# OS-2024-Badge-Schematic-REV1.net
KiCad netlist of a schematic drawn in Altium Designer
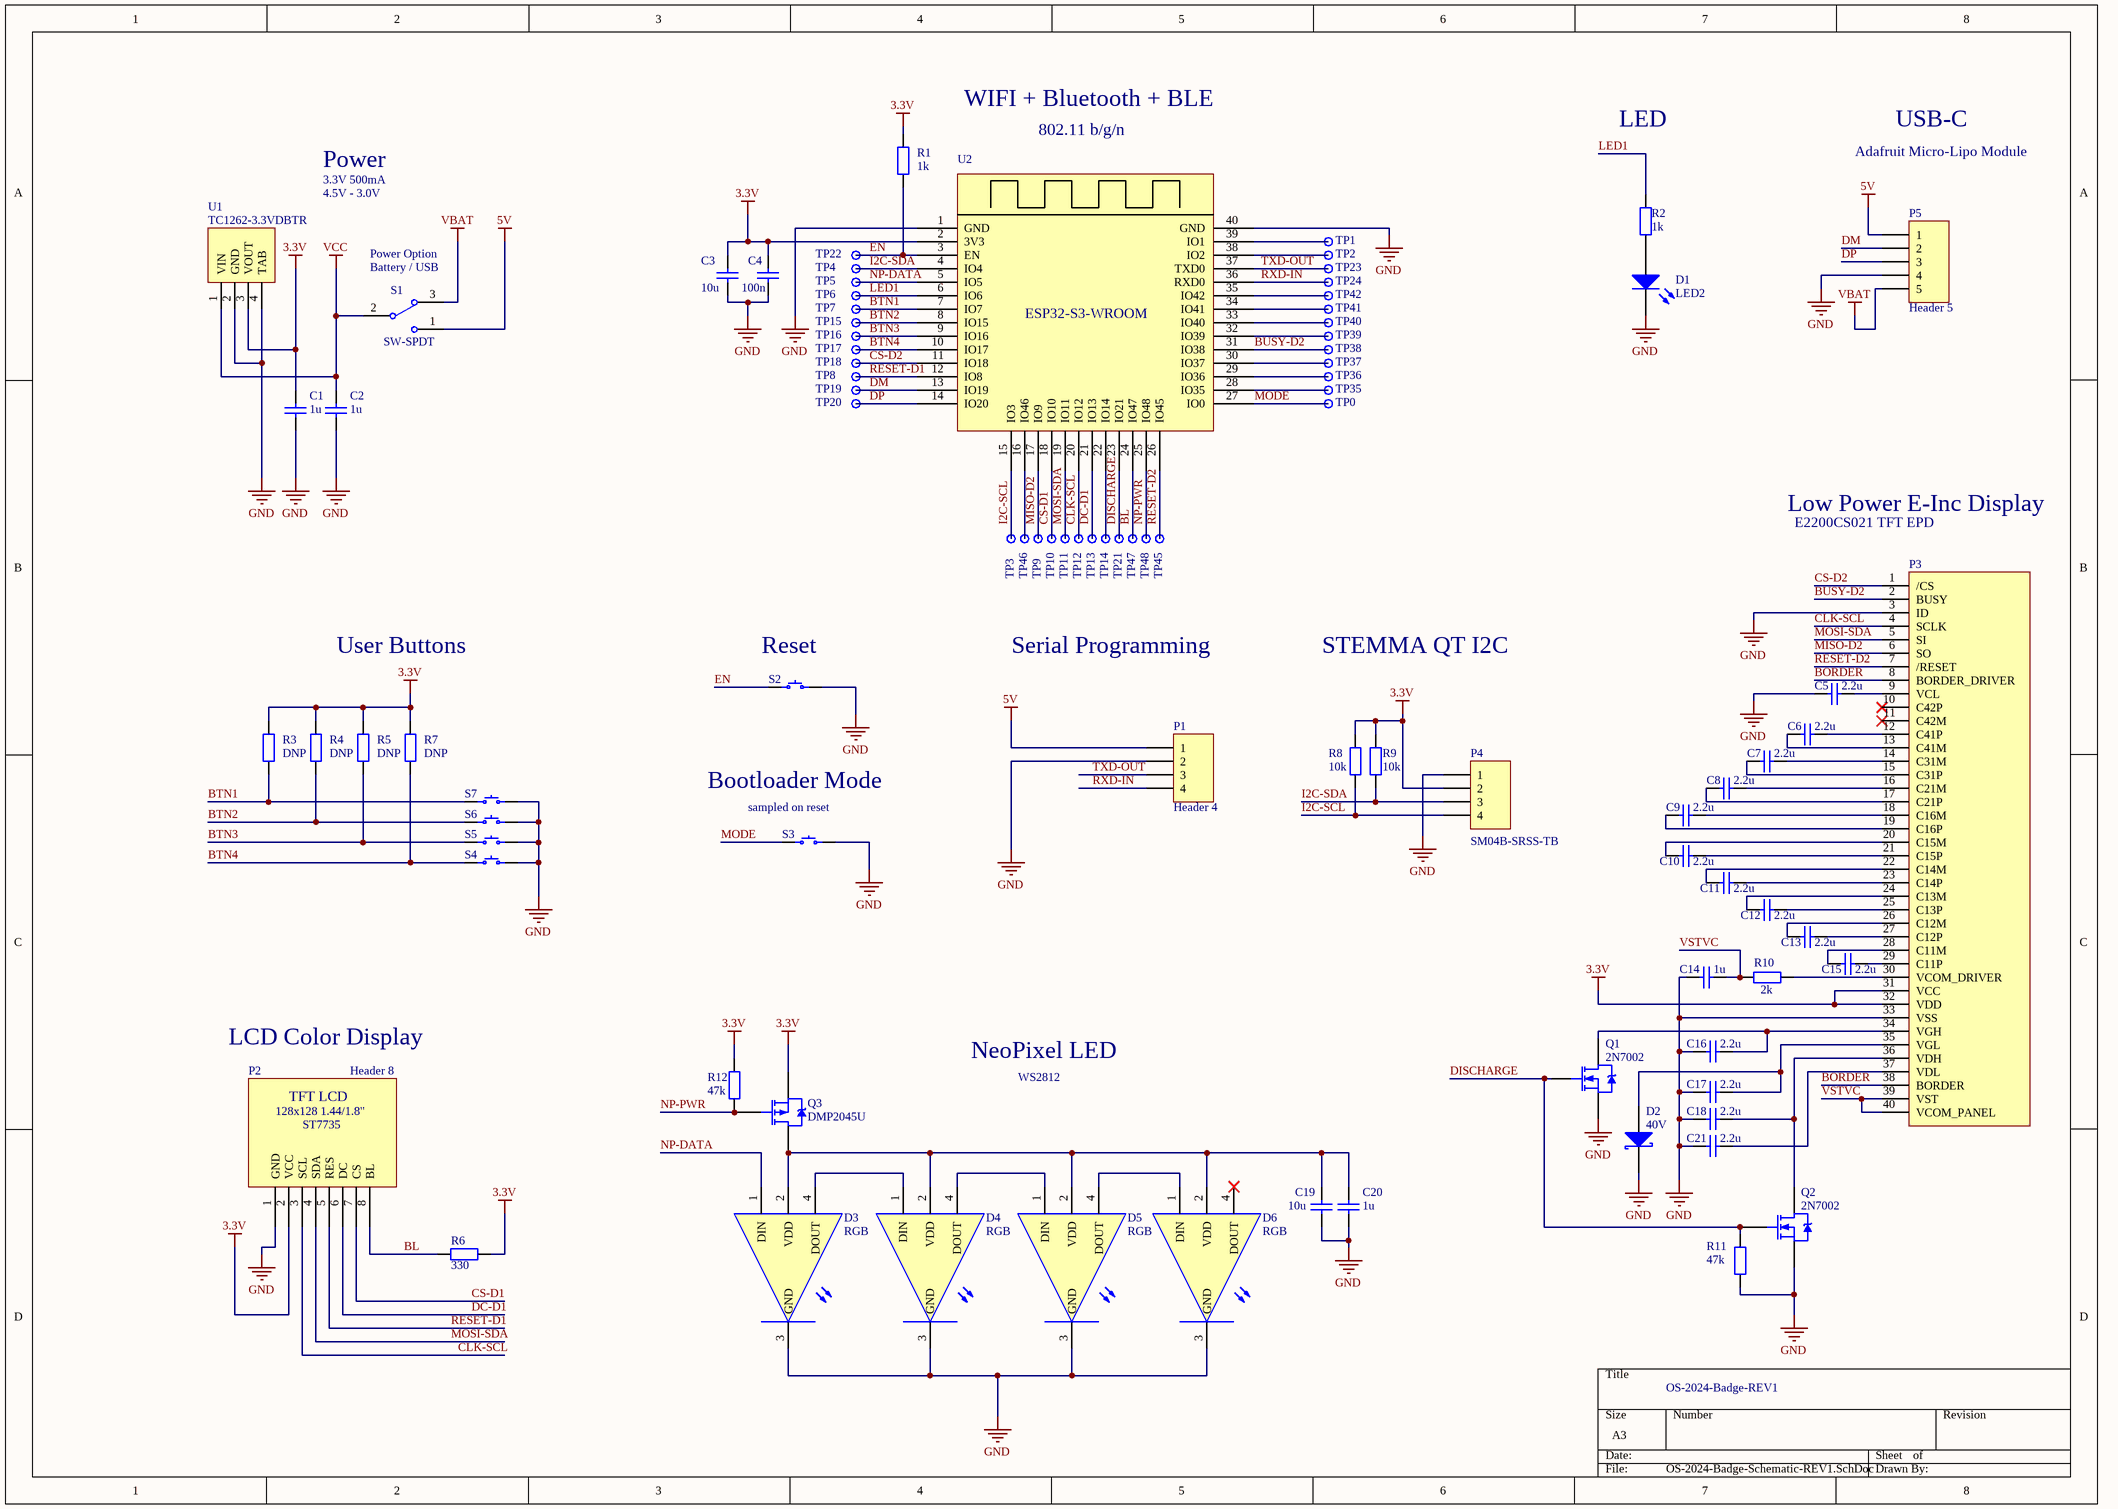
[diagram p0: OS-2024-Badge-Schematic-REV1.SchDoc]

(export (version "E")
  (design (tool "Eeschema 10.0.6"))
  (components
    (comp (ref "C1")
      (value "1u")
      (footprint "0603C")
      (description "CAP CER 1UF 50V Z5U 0603")
      (fields
        (field (name "MANUFACTURER") "Murata Electronics North America")
        (field (name "MANUFACTURER PART NUMBER") "GRT188R61H105ME13D")
      )
      (libsource (lib "Miscellaneous Devices") (part "Cap"))
    )
    (comp (ref "C2")
      (value "1u")
      (footprint "0603C")
      (description "CAP CER 1UF 50V Z5U 0603")
      (fields
        (field (name "MANUFACTURER") "Murata Electronics North America")
        (field (name "MANUFACTURER PART NUMBER") "GRT188R61H105ME13D")
      )
      (libsource (lib "Miscellaneous Devices") (part "Cap"))
    )
    (comp (ref "C3")
      (value "10u")
      (footprint "0603C")
      (description "CAP CER 10UF 10V X5R 0603")
      (fields
        (field (name "MANUFACTURER") "Murata Electronics North America")
        (field (name "MANUFACTURER PART NUMBER") "GRN188R61A106KE69J")
      )
      (libsource (lib "Miscellaneous Devices") (part "Cap"))
    )
    (comp (ref "C4")
      (value "100n")
      (footprint "0603C")
      (description "CAP CER .1UF 10V X7R 0603")
      (fields
        (field (name "MANUFACTURER") "Wurth Electronics Inc.")
        (field (name "MANUFACTURER PART NUMBER") "885012206020")
      )
      (libsource (lib "Miscellaneous Devices") (part "Cap"))
    )
    (comp (ref "C5")
      (value "2.2u")
      (footprint "0603C")
      (description "CAP CER 2.2UF 10V X5R 0603")
      (fields
        (field (name "MANUFACTURER") "Cal-Chip Electronics, Inc.")
        (field (name "MANUFACTURER PART NUMBER") "GMC10X5R225M10NT")
      )
      (libsource (lib "Miscellaneous Devices") (part "Cap"))
    )
    (comp (ref "C6")
      (value "2.2u")
      (footprint "0603C")
      (description "CAP CER 2.2UF 10V X5R 0603")
      (fields
        (field (name "MANUFACTURER") "Cal-Chip Electronics, Inc.")
        (field (name "MANUFACTURER PART NUMBER") "GMC10X5R225M10NT")
      )
      (libsource (lib "Miscellaneous Devices") (part "Cap"))
    )
    (comp (ref "C7")
      (value "2.2u")
      (footprint "0603C")
      (description "CAP CER 2.2UF 10V X5R 0603")
      (fields
        (field (name "MANUFACTURER") "Cal-Chip Electronics, Inc.")
        (field (name "MANUFACTURER PART NUMBER") "GMC10X5R225M10NT")
      )
      (libsource (lib "Miscellaneous Devices") (part "Cap"))
    )
    (comp (ref "C8")
      (value "2.2u")
      (footprint "0603C")
      (description "CAP CER 2.2UF 10V X5R 0603")
      (fields
        (field (name "MANUFACTURER") "Cal-Chip Electronics, Inc.")
        (field (name "MANUFACTURER PART NUMBER") "GMC10X5R225M10NT")
      )
      (libsource (lib "Miscellaneous Devices") (part "Cap"))
    )
    (comp (ref "C9")
      (value "2.2u")
      (footprint "0603C")
      (description "CAP CER 2.2UF 10V X5R 0603")
      (fields
        (field (name "MANUFACTURER") "Cal-Chip Electronics, Inc.")
        (field (name "MANUFACTURER PART NUMBER") "GMC10X5R225M10NT")
      )
      (libsource (lib "Miscellaneous Devices") (part "Cap"))
    )
    (comp (ref "C10")
      (value "2.2u")
      (footprint "0603C")
      (description "CAP CER 2.2UF 10V X5R 0603")
      (fields
        (field (name "MANUFACTURER") "Cal-Chip Electronics, Inc.")
        (field (name "MANUFACTURER PART NUMBER") "GMC10X5R225M10NT")
      )
      (libsource (lib "Miscellaneous Devices") (part "Cap"))
    )
    (comp (ref "C11")
      (value "2.2u")
      (footprint "0603C")
      (description "CAP CER 2.2UF 10V X5R 0603")
      (fields
        (field (name "MANUFACTURER") "Cal-Chip Electronics, Inc.")
        (field (name "MANUFACTURER PART NUMBER") "GMC10X5R225M10NT")
      )
      (libsource (lib "Miscellaneous Devices") (part "Cap"))
    )
    (comp (ref "C12")
      (value "2.2u")
      (footprint "0603C")
      (description "CAP CER 2.2UF 10V X5R 0603")
      (fields
        (field (name "MANUFACTURER") "Cal-Chip Electronics, Inc.")
        (field (name "MANUFACTURER PART NUMBER") "GMC10X5R225M10NT")
      )
      (libsource (lib "Miscellaneous Devices") (part "Cap"))
    )
    (comp (ref "C13")
      (value "2.2u")
      (footprint "0603C")
      (description "CAP CER 2.2UF 10V X5R 0603")
      (fields
        (field (name "MANUFACTURER") "Cal-Chip Electronics, Inc.")
        (field (name "MANUFACTURER PART NUMBER") "GMC10X5R225M10NT")
      )
      (libsource (lib "Miscellaneous Devices") (part "Cap"))
    )
    (comp (ref "C14")
      (value "1u")
      (footprint "0603C")
      (description "CAP CER 1UF 50V Z5U 0603")
      (fields
        (field (name "MANUFACTURER") "Murata Electronics North America")
        (field (name "MANUFACTURER PART NUMBER") "GRT188R61H105ME13D")
      )
      (libsource (lib "Miscellaneous Devices") (part "Cap"))
    )
    (comp (ref "C15")
      (value "2.2u")
      (footprint "0603C")
      (description "CAP CER 2.2UF 10V X5R 0603")
      (fields
        (field (name "MANUFACTURER") "Cal-Chip Electronics, Inc.")
        (field (name "MANUFACTURER PART NUMBER") "GMC10X5R225M10NT")
      )
      (libsource (lib "Miscellaneous Devices") (part "Cap"))
    )
    (comp (ref "C16")
      (value "2.2u")
      (footprint "0603C")
      (description "CAP CER 2.2UF 10V X5R 0603")
      (fields
        (field (name "MANUFACTURER") "Cal-Chip Electronics, Inc.")
        (field (name "MANUFACTURER PART NUMBER") "GMC10X5R225M10NT")
      )
      (libsource (lib "Miscellaneous Devices") (part "Cap"))
    )
    (comp (ref "C17")
      (value "2.2u")
      (footprint "0603C")
      (description "CAP CER 2.2UF 10V X5R 0603")
      (fields
        (field (name "MANUFACTURER") "Cal-Chip Electronics, Inc.")
        (field (name "MANUFACTURER PART NUMBER") "GMC10X5R225M10NT")
      )
      (libsource (lib "Miscellaneous Devices") (part "Cap"))
    )
    (comp (ref "C18")
      (value "2.2u")
      (footprint "0603C")
      (description "CAP CER 2.2UF 10V X5R 0603")
      (fields
        (field (name "MANUFACTURER") "Cal-Chip Electronics, Inc.")
        (field (name "MANUFACTURER PART NUMBER") "GMC10X5R225M10NT")
      )
      (libsource (lib "Miscellaneous Devices") (part "Cap"))
    )
    (comp (ref "C19")
      (value "10u")
      (footprint "0603C")
      (description "CAP CER 10UF 10V X5R 0603")
      (fields
        (field (name "MANUFACTURER") "Murata Electronics North America")
        (field (name "MANUFACTURER PART NUMBER") "GRN188R61A106KE69J")
      )
      (libsource (lib "Miscellaneous Devices") (part "Cap"))
    )
    (comp (ref "C20")
      (value "1u")
      (footprint "0603C")
      (description "CAP CER 1UF 50V Z5U 0603")
      (fields
        (field (name "MANUFACTURER") "Murata Electronics North America")
        (field (name "MANUFACTURER PART NUMBER") "GRT188R61H105ME13D")
      )
      (libsource (lib "Miscellaneous Devices") (part "Cap"))
    )
    (comp (ref "C21")
      (value "2.2u")
      (footprint "0603C")
      (description "CAP CER 2.2UF 10V X5R 0603")
      (fields
        (field (name "MANUFACTURER") "Cal-Chip Electronics, Inc.")
        (field (name "MANUFACTURER PART NUMBER") "GMC10X5R225M10NT")
      )
      (libsource (lib "Miscellaneous Devices") (part "Cap"))
    )
    (comp (ref "D1")
      (value "LED2")
      (footprint "0603LED")
      (description "LED ORANGE CLEAR CHIP SMD")
      (fields
        (field (name "DISTRIBUTOR PART NUMBER") "754-1120-1-ND")
        (field (name "MANUFACTURER") "Kingbright")
      )
      (libsource (lib "Miscellaneous Devices") (part "LED2"))
    )
    (comp (ref "D2")
      (value "40V")
      (footprint "SOD-123FL")
      (description "DIODE SCHOTTKY 40V 2A SOD123FL")
      (fields
        (field (name "DISTRIBUTOR PART NUMBER") "3757-SS2040FL_R1_00001CT-ND")
        (field (name "MANUFACTURER") "Panjit International Inc.")
      )
      (libsource (lib "Miscellaneous Devices") (part "Diode BAT17"))
    )
    (comp (ref "D3")
      (value "RGB")
      (footprint "COM-12986")
      (description "ADDRESS LED DISCR SERIAL RGB")
      (fields
        (field (name "DISTRIBUTOR PART NUMBER") "1568-1213-ND")
        (field (name "MANUFACTURER") "Spark Fun")
      )
      (libsource (lib "2024-Badge-Altium-Project-REV0_1") (part "LED2_1"))
    )
    (comp (ref "D4")
      (value "RGB")
      (footprint "COM-12986")
      (description "ADDRESS LED DISCR SERIAL RGB")
      (fields
        (field (name "DISTRIBUTOR PART NUMBER") "1568-1213-ND")
        (field (name "MANUFACTURER") "Spark Fun")
      )
      (libsource (lib "2024-Badge-Altium-Project-REV0_1") (part "LED2_1"))
    )
    (comp (ref "D5")
      (value "RGB")
      (footprint "COM-12986")
      (description "ADDRESS LED DISCR SERIAL RGB")
      (fields
        (field (name "DISTRIBUTOR PART NUMBER") "1568-1213-ND")
        (field (name "MANUFACTURER") "Spark Fun")
      )
      (libsource (lib "2024-Badge-Altium-Project-REV0_1") (part "LED2_1"))
    )
    (comp (ref "D6")
      (value "RGB")
      (footprint "COM-12986")
      (description "ADDRESS LED DISCR SERIAL RGB")
      (fields
        (field (name "DISTRIBUTOR PART NUMBER") "1568-1213-ND")
        (field (name "MANUFACTURER") "Spark Fun")
      )
      (libsource (lib "2024-Badge-Altium-Project-REV0_1") (part "LED2_1"))
    )
    (comp (ref "P1")
      (value "Header 4")
      (footprint "HDR1X4")
      (description "Header, 4-Pin")
      (fields
        (field (name "DISTRIBUTOR PART NUMBER") "732-5317-ND")
        (field (name "MANUFACTURER") "Wurth Elektronik")
      )
      (libsource (lib "Miscellaneous Connectors") (part "Header 4"))
    )
    (comp (ref "P2")
      (value "Header 8")
      (footprint "TFT144SPI")
      (description "1.44\" 128x128 65K SPI Full Color TFT LCD Display Module ST7735 OLED for Arduino")
      (fields (field (name "DISTRIBUTOR PART NUMBER") "ED90446-ND") (field (name "MANUFACTURER") "Mill-Max"))
      (libsource (lib "OS-2019-Badge-Schematic-REV0") (part "Display_128_128"))
    )
    (comp (ref "P3")
      (value "CONN FPC BOTTOM 40POS 0.5MM R/A")
      (footprint "AMPHENOL_62684-401100AHLF")
      (fields
        (field (name "DISTRIBUTOR PART NUMBER") "609-62684-401100AHLFTR-ND")
        (field (name "MANUFACTURER") "Amphenol ICC (FCI)")
        (field (name "MANUFACTURER PART NUMBER") "62684-401100AHLF")
      )
      (libsource (lib "2024-Badge-Altium-Project-REV1") (part "Header 40"))
    )
    (comp (ref "P4")
      (value "SM04B-SRSS-TB")
      (footprint "SM04B-TRSS-TB")
      (description "CONN HEADER SMD R/A 4POS 1MM")
      (fields
        (field (name "DISTRIBUTOR PART NUMBER") "455-SM04B-SRSS-TBCT-ND")
        (field (name "MANUFACTURER") "JST Sales America Inc.")
      )
      (libsource (lib "2024-Badge-Altium-Project-REV0_1") (part "Header 5"))
    )
    (comp (ref "P5")
      (value "Header 5")
      (footprint "Micro-Lipo-USBC")
      (description "Adafruit Micro-Lipo Charger for LiPoly Batt with USB Type C Jack")
      (fields (field (name "DISTRIBUTOR PART NUMBER") "ED90446-ND") (field (name "MANUFACTURER") "Mill-Max"))
      (libsource (lib "Miscellaneous Connectors") (part "Header 5"))
    )
    (comp (ref "Q1")
      (value "2N7002")
      (footprint "SOT-23-N")
      (description "MOSFET N-CH 60V 280MA SOT23-3")
      (fields
        (field (name "DISTRIBUTOR PART NUMBER") "4878-2N7002CT-ND")
        (field (name "MANUFACTURER") "Diotec Semiconductor")
      )
      (libsource (lib "Miscellaneous Devices") (part "NMOS-2"))
    )
    (comp (ref "Q2")
      (value "2N7002")
      (footprint "SOT-23-N")
      (description "MOSFET N-CH 60V 280MA SOT23-3")
      (fields
        (field (name "DISTRIBUTOR PART NUMBER") "4878-2N7002CT-ND")
        (field (name "MANUFACTURER") "Diotec Semiconductor")
      )
      (libsource (lib "Miscellaneous Devices") (part "NMOS-2"))
    )
    (comp (ref "Q3")
      (value "DMP2045U")
      (footprint "SOT-23-P")
      (description "P-Channel Power MOSFET")
      (fields
        (field (name "DISTRIBUTOR PART NUMBER") "DMP2045U-7DICT-ND")
        (field (name "MANUFACTURER") "Diodes Incorporated")
      )
      (libsource (lib "Miscellaneous Devices") (part "PMOS-2"))
    )
    (comp (ref "R1")
      (value "1k")
      (footprint "0603R")
      (description "RES SMD 1K OHM 5% 1/10W 0603")
      (fields
        (field (name "MANUFACTURER") "Yageo")
        (field (name "MANUFACTURER PART NUMBER") "RC0603JR-071KL")
      )
      (libsource (lib "") (part "Res2_2"))
    )
    (comp (ref "R2")
      (value "1k")
      (footprint "0603R")
      (description "RES SMD 1K OHM 5% 1/10W 0603")
      (fields
        (field (name "MANUFACTURER") "Yageo")
        (field (name "MANUFACTURER PART NUMBER") "RC0603JR-071KL")
      )
      (libsource (lib "") (part "Res2_1"))
    )
    (comp (ref "R3")
      (value "DNP")
      (footprint "0603R")
      (description "RES SMD 1K OHM 5% 1/10W 0603")
      (fields (field (name "MANUFACTURER") "NONE"))
      (libsource (lib "") (part "Res2_2"))
    )
    (comp (ref "R4")
      (value "DNP")
      (footprint "0603R")
      (description "RES SMD 1K OHM 5% 1/10W 0603")
      (fields (field (name "MANUFACTURER") "NONE"))
      (libsource (lib "") (part "Res2_2"))
    )
    (comp (ref "R5")
      (value "DNP")
      (footprint "0603R")
      (description "RES SMD 1K OHM 5% 1/10W 0603")
      (fields (field (name "MANUFACTURER") "NONE"))
      (libsource (lib "") (part "Res2_2"))
    )
    (comp (ref "R6")
      (value "330")
      (footprint "0603R")
      (description "RES SMD 330 OHM 5% 1/10W 0603")
      (fields
        (field (name "MANUFACTURER") "Yageo")
        (field (name "MANUFACTURER PART NUMBER") "RC0603JR-07330RL")
      )
      (libsource (lib "Miscellaneous Devices") (part "Res2"))
    )
    (comp (ref "R7")
      (value "DNP")
      (footprint "0603R")
      (description "RES SMD 1K OHM 5% 1/10W 0603")
      (fields (field (name "MANUFACTURER") "NONE"))
      (libsource (lib "") (part "Res2_2"))
    )
    (comp (ref "R8")
      (value "10k")
      (footprint "0603R")
      (description "RES SMD 10K OHM 5% 1/10W 0603")
      (fields
        (field (name "MANUFACTURER") "Yageo")
        (field (name "MANUFACTURER PART NUMBER") "RC0603JR-0710KL")
      )
      (libsource (lib "") (part "Res2_1"))
    )
    (comp (ref "R9")
      (value "10k")
      (footprint "0603R")
      (description "RES SMD 10K OHM 5% 1/10W 0603")
      (fields
        (field (name "MANUFACTURER") "Yageo")
        (field (name "MANUFACTURER PART NUMBER") "RC0603JR-0710KL")
      )
      (libsource (lib "") (part "Res2_1"))
    )
    (comp (ref "R10")
      (value "2k")
      (footprint "0603R")
      (description "RES SMD 2K OHM 5% 1/10W 0603")
      (fields
        (field (name "MANUFACTURER") "Yageo")
        (field (name "MANUFACTURER PART NUMBER") "RC0603JR-072KL")
      )
      (libsource (lib "Miscellaneous Devices") (part "Res2"))
    )
    (comp (ref "R11")
      (value "47k")
      (footprint "0603R")
      (description "RES SMD 47K OHM 5% 1/10W 0603")
      (fields
        (field (name "MANUFACTURER") "Yageo")
        (field (name "MANUFACTURER PART NUMBER") "RC0603JR-0747KL")
      )
      (libsource (lib "") (part "Res2_1"))
    )
    (comp (ref "R12")
      (value "47k")
      (footprint "0603R")
      (description "RES SMD 47K OHM 5% 1/10W 0603")
      (fields
        (field (name "MANUFACTURER") "Yageo")
        (field (name "MANUFACTURER PART NUMBER") "RC0603JR-0747KL")
      )
      (libsource (lib "") (part "Res2_1"))
    )
    (comp (ref "S1")
      (value "SW-SPDT")
      (footprint "HDR1X3")
      (description "SWITCH SLIDE SPDT 200MA 30V")
      (fields (field (name "MANUFACTURER") "E-Switch") (field (name "MANUFACTURER PART NUMBER") "EG1218"))
      (libsource (lib "Miscellaneous Devices") (part "SW-SPDT"))
    )
    (comp (ref "S2")
      (value "SPST-NO")
      (footprint "PTS636SL43LFS")
      (description "Tactile Switch SPST-NO Top Actuated Through Hole")
      (fields (field (name "DISTRIBUTOR PART NUMBER") "CKN12301-ND") (field (name "MANUFACTURER") "C&K"))
      (libsource (lib "Button") (part "SPST-NO 2 PIN"))
    )
    (comp (ref "S3")
      (value "SPST-NO")
      (footprint "PTS636SL43LFS")
      (description "Tactile Switch SPST-NO Top Actuated Through Hole")
      (fields (field (name "DISTRIBUTOR PART NUMBER") "CKN12301-ND") (field (name "MANUFACTURER") "C&K"))
      (libsource (lib "Button") (part "SPST-NO 2 PIN"))
    )
    (comp (ref "S4")
      (value "SPST-NO")
      (footprint "PTS636SL43LFS")
      (description "Tactile Switch SPST-NO Top Actuated Through Hole")
      (fields (field (name "DISTRIBUTOR PART NUMBER") "CKN12301-ND") (field (name "MANUFACTURER") "C&K"))
      (libsource (lib "Button") (part "SPST-NO 2 PIN"))
    )
    (comp (ref "S5")
      (value "SPST-NO")
      (footprint "PTS636SL43LFS")
      (description "Tactile Switch SPST-NO Top Actuated Through Hole")
      (fields (field (name "DISTRIBUTOR PART NUMBER") "CKN12301-ND") (field (name "MANUFACTURER") "C&K"))
      (libsource (lib "Button") (part "SPST-NO 2 PIN"))
    )
    (comp (ref "S6")
      (value "SPST-NO")
      (footprint "PTS636SL43LFS")
      (description "Tactile Switch SPST-NO Top Actuated Through Hole")
      (fields (field (name "DISTRIBUTOR PART NUMBER") "CKN12301-ND") (field (name "MANUFACTURER") "C&K"))
      (libsource (lib "Button") (part "SPST-NO 2 PIN"))
    )
    (comp (ref "S7")
      (value "SPST-NO")
      (footprint "PTS636SL43LFS")
      (description "Tactile Switch SPST-NO Top Actuated Through Hole")
      (fields (field (name "DISTRIBUTOR PART NUMBER") "CKN12301-ND") (field (name "MANUFACTURER") "C&K"))
      (libsource (lib "Button") (part "SPST-NO 2 PIN"))
    )
    (comp (ref "TP0")
      (value "Test Point")
      (footprint "Testpoint")
      (description "Test Point Do Not Populate")
      (fields (field (name "MANUFACTURER") "NONE"))
      (libsource (lib "*") (part "TestPoint"))
    )
    (comp (ref "TP1")
      (value "Test Point")
      (footprint "Testpoint")
      (description "Test Point Do Not Populate")
      (fields (field (name "MANUFACTURER") "NONE"))
      (libsource (lib "*") (part "TestPoint"))
    )
    (comp (ref "TP2")
      (value "Test Point")
      (footprint "Testpoint")
      (description "Test Point Do Not Populate")
      (fields (field (name "MANUFACTURER") "NONE"))
      (libsource (lib "*") (part "TestPoint"))
    )
    (comp (ref "TP3")
      (value "Test Point")
      (footprint "Testpoint")
      (description "Test Point Do Not Populate")
      (fields (field (name "MANUFACTURER") "NONE"))
      (libsource (lib "*") (part "TestPoint"))
    )
    (comp (ref "TP4")
      (value "Test Point")
      (footprint "Testpoint")
      (description "Test Point Do Not Populate")
      (fields (field (name "MANUFACTURER") "NONE"))
      (libsource (lib "*") (part "TestPoint"))
    )
    (comp (ref "TP5")
      (value "Test Point")
      (footprint "Testpoint")
      (description "Test Point Do Not Populate")
      (fields (field (name "MANUFACTURER") "NONE"))
      (libsource (lib "*") (part "TestPoint"))
    )
    (comp (ref "TP6")
      (value "Test Point")
      (footprint "Testpoint")
      (description "Test Point Do Not Populate")
      (fields (field (name "MANUFACTURER") "NONE"))
      (libsource (lib "*") (part "TestPoint"))
    )
    (comp (ref "TP7")
      (value "Test Point")
      (footprint "Testpoint")
      (description "Test Point Do Not Populate")
      (fields (field (name "MANUFACTURER") "NONE"))
      (libsource (lib "*") (part "TestPoint"))
    )
    (comp (ref "TP8")
      (value "Test Point")
      (footprint "Testpoint")
      (description "Test Point Do Not Populate")
      (fields (field (name "MANUFACTURER") "NONE"))
      (libsource (lib "*") (part "TestPoint"))
    )
    (comp (ref "TP9")
      (value "Test Point")
      (footprint "Testpoint")
      (description "Test Point Do Not Populate")
      (fields (field (name "MANUFACTURER") "NONE"))
      (libsource (lib "*") (part "TestPoint"))
    )
    (comp (ref "TP10")
      (value "Test Point")
      (footprint "Testpoint")
      (description "Test Point Do Not Populate")
      (fields (field (name "MANUFACTURER") "NONE"))
      (libsource (lib "*") (part "TestPoint"))
    )
    (comp (ref "TP11")
      (value "Test Point")
      (footprint "Testpoint")
      (description "Test Point Do Not Populate")
      (fields (field (name "MANUFACTURER") "NONE"))
      (libsource (lib "*") (part "TestPoint"))
    )
    (comp (ref "TP12")
      (value "Test Point")
      (footprint "Testpoint")
      (description "Test Point Do Not Populate")
      (fields (field (name "MANUFACTURER") "NONE"))
      (libsource (lib "*") (part "TestPoint"))
    )
    (comp (ref "TP13")
      (value "Test Point")
      (footprint "Testpoint")
      (description "Test Point Do Not Populate")
      (fields (field (name "MANUFACTURER") "NONE"))
      (libsource (lib "*") (part "TestPoint"))
    )
    (comp (ref "TP14")
      (value "Test Point")
      (footprint "Testpoint")
      (description "Test Point Do Not Populate")
      (fields (field (name "MANUFACTURER") "NONE"))
      (libsource (lib "*") (part "TestPoint"))
    )
    (comp (ref "TP15")
      (value "Test Point")
      (footprint "Testpoint")
      (description "Test Point Do Not Populate")
      (fields (field (name "MANUFACTURER") "NONE"))
      (libsource (lib "*") (part "TestPoint"))
    )
    (comp (ref "TP16")
      (value "Test Point")
      (footprint "Testpoint")
      (description "Test Point Do Not Populate")
      (fields (field (name "MANUFACTURER") "NONE"))
      (libsource (lib "*") (part "TestPoint"))
    )
    (comp (ref "TP17")
      (value "Test Point")
      (footprint "Testpoint")
      (description "Test Point Do Not Populate")
      (fields (field (name "MANUFACTURER") "NONE"))
      (libsource (lib "*") (part "TestPoint"))
    )
    (comp (ref "TP18")
      (value "Test Point")
      (footprint "Testpoint")
      (description "Test Point Do Not Populate")
      (fields (field (name "MANUFACTURER") "NONE"))
      (libsource (lib "*") (part "TestPoint"))
    )
    (comp (ref "TP19")
      (value "Test Point")
      (footprint "Testpoint")
      (description "Test Point Do Not Populate")
      (fields (field (name "MANUFACTURER") "NONE"))
      (libsource (lib "*") (part "TestPoint"))
    )
    (comp (ref "TP20")
      (value "Test Point")
      (footprint "Testpoint")
      (description "Test Point Do Not Populate")
      (fields (field (name "MANUFACTURER") "NONE"))
      (libsource (lib "*") (part "TestPoint"))
    )
    (comp (ref "TP21")
      (value "Test Point")
      (footprint "Testpoint")
      (description "Test Point Do Not Populate")
      (fields (field (name "MANUFACTURER") "NONE"))
      (libsource (lib "*") (part "TestPoint"))
    )
    (comp (ref "TP22")
      (value "Test Point")
      (footprint "Testpoint")
      (description "Test Point Do Not Populate")
      (fields (field (name "MANUFACTURER") "NONE"))
      (libsource (lib "*") (part "TestPoint"))
    )
    (comp (ref "TP23")
      (value "Test Point")
      (footprint "Testpoint")
      (description "Test Point Do Not Populate")
      (fields (field (name "MANUFACTURER") "NONE"))
      (libsource (lib "*") (part "TestPoint"))
    )
    (comp (ref "TP24")
      (value "Test Point")
      (footprint "Testpoint")
      (description "Test Point Do Not Populate")
      (fields (field (name "MANUFACTURER") "NONE"))
      (libsource (lib "*") (part "TestPoint"))
    )
    (comp (ref "TP35")
      (value "Test Point")
      (footprint "Testpoint")
      (description "Test Point Do Not Populate")
      (fields (field (name "MANUFACTURER") "NONE"))
      (libsource (lib "*") (part "TestPoint"))
    )
    (comp (ref "TP36")
      (value "Test Point")
      (footprint "Testpoint")
      (description "Test Point Do Not Populate")
      (fields (field (name "MANUFACTURER") "NONE"))
      (libsource (lib "*") (part "TestPoint"))
    )
    (comp (ref "TP37")
      (value "Test Point")
      (footprint "Testpoint")
      (description "Test Point Do Not Populate")
      (fields (field (name "MANUFACTURER") "NONE"))
      (libsource (lib "*") (part "TestPoint"))
    )
    (comp (ref "TP38")
      (value "Test Point")
      (footprint "Testpoint")
      (description "Test Point Do Not Populate")
      (fields (field (name "MANUFACTURER") "NONE"))
      (libsource (lib "*") (part "TestPoint"))
    )
    (comp (ref "TP39")
      (value "Test Point")
      (footprint "Testpoint")
      (description "Test Point Do Not Populate")
      (fields (field (name "MANUFACTURER") "NONE"))
      (libsource (lib "*") (part "TestPoint"))
    )
    (comp (ref "TP40")
      (value "Test Point")
      (footprint "Testpoint")
      (description "Test Point Do Not Populate")
      (fields (field (name "MANUFACTURER") "NONE"))
      (libsource (lib "*") (part "TestPoint"))
    )
    (comp (ref "TP41")
      (value "Test Point")
      (footprint "Testpoint")
      (description "Test Point Do Not Populate")
      (fields (field (name "MANUFACTURER") "NONE"))
      (libsource (lib "*") (part "TestPoint"))
    )
    (comp (ref "TP42")
      (value "Test Point")
      (footprint "Testpoint")
      (description "Test Point Do Not Populate")
      (fields (field (name "MANUFACTURER") "NONE"))
      (libsource (lib "*") (part "TestPoint"))
    )
    (comp (ref "TP45")
      (value "Test Point")
      (footprint "Testpoint")
      (description "Test Point Do Not Populate")
      (fields (field (name "MANUFACTURER") "NONE"))
      (libsource (lib "*") (part "TestPoint"))
    )
    (comp (ref "TP46")
      (value "Test Point")
      (footprint "Testpoint")
      (description "Test Point Do Not Populate")
      (fields (field (name "MANUFACTURER") "NONE"))
      (libsource (lib "*") (part "TestPoint"))
    )
    (comp (ref "TP47")
      (value "Test Point")
      (footprint "Testpoint")
      (description "Test Point Do Not Populate")
      (fields (field (name "MANUFACTURER") "NONE"))
      (libsource (lib "*") (part "TestPoint"))
    )
    (comp (ref "TP48")
      (value "Test Point")
      (footprint "Testpoint")
      (description "Test Point Do Not Populate")
      (fields (field (name "MANUFACTURER") "NONE"))
      (libsource (lib "*") (part "TestPoint"))
    )
    (comp (ref "U1")
      (value "TC1262-3.3VDBTR")
      (footprint "OS-2019-Badge-REV0:SOT-223-2")
      (description "IC REG LINEAR 3.3V 500mA SOT223-3")
      (fields
        (field (name "MANUFACTURER") "Microchip Technology")
        (field (name "DISTRIBUTOR PART NUMBER") "TC1262-3.3VDBCT-ND")
      )
      (libsource (lib "OS-2019-Badge-Schematic-REV0") (part "Header 3"))
    )
    (comp (ref "U2")
      (value "ESP32-S3-WROOM")
      (footprint "ESP32-S3-WROOM-1-N16R8")
      (description "Bluetooth, WiFi 802.11b/g/n, Bluetooth v5.0 Transceiver Module 2.4GHz PCB Trace Surface Mount")
      (fields
        (field (name "MANUFACTURER") "Espressif Systems")
        (field (name "MANUFACTURER PART NUMBER") "ESP32-S3-WROOM-1-N16R8")
      )
      (libsource (lib "2024-Badge-Altium-Project-REV0_1") (part "ESP32-S3-WROOM"))
    )
  )
  (nets
    (net (code "1") (name "/BL") (class "Default")
      (node (ref "P2") (pin "8") (pinfunction "BL_8") (pintype "passive"))
      (node (ref "R6") (pin "1") (pinfunction "1_1") (pintype "passive"))
      (node (ref "TP47") (pin "1") (pinfunction "1_1") (pintype "passive"))
      (node (ref "U2") (pin "24") (pinfunction "IO47_24") (pintype "passive"))
    )
    (net (code "2") (name "/BORDER") (class "Default")
      (node (ref "P3") (pin "38") (pinfunction "BORDER_38") (pintype "passive"))
      (node (ref "P3") (pin "8") (pinfunction "BORDER_DRIVER_8") (pintype "passive"))
    )
    (net (code "3") (name "/BTN1") (class "Default")
      (node (ref "R3") (pin "1") (pinfunction "1_1") (pintype "passive"))
      (node (ref "S7") (pin "1") (pinfunction "1_1") (pintype "passive"))
      (node (ref "TP7") (pin "1") (pinfunction "1_1") (pintype "passive"))
      (node (ref "U2") (pin "7") (pinfunction "IO7_7") (pintype "passive"))
    )
    (net (code "4") (name "/BTN2") (class "Default")
      (node (ref "R4") (pin "1") (pinfunction "1_1") (pintype "passive"))
      (node (ref "S6") (pin "1") (pinfunction "1_1") (pintype "passive"))
      (node (ref "TP15") (pin "1") (pinfunction "1_1") (pintype "passive"))
      (node (ref "U2") (pin "8") (pinfunction "IO15_8") (pintype "passive"))
    )
    (net (code "5") (name "/BTN3") (class "Default")
      (node (ref "R5") (pin "1") (pinfunction "1_1") (pintype "passive"))
      (node (ref "S5") (pin "1") (pinfunction "1_1") (pintype "passive"))
      (node (ref "TP16") (pin "1") (pinfunction "1_1") (pintype "passive"))
      (node (ref "U2") (pin "9") (pinfunction "IO16_9") (pintype "passive"))
    )
    (net (code "6") (name "/BTN4") (class "Default")
      (node (ref "R7") (pin "1") (pinfunction "1_1") (pintype "passive"))
      (node (ref "S4") (pin "1") (pinfunction "1_1") (pintype "passive"))
      (node (ref "TP17") (pin "1") (pinfunction "1_1") (pintype "passive"))
      (node (ref "U2") (pin "10") (pinfunction "IO17_10") (pintype "passive"))
    )
    (net (code "7") (name "/BUSY-D2") (class "Default")
      (node (ref "P3") (pin "2") (pinfunction "BUSY_2") (pintype "passive"))
      (node (ref "TP38") (pin "1") (pinfunction "1_1") (pintype "passive"))
      (node (ref "U2") (pin "31") (pinfunction "IO38_31") (pintype "passive"))
    )
    (net (code "8") (name "/CLK-SCL") (class "Default")
      (node (ref "P2") (pin "3") (pinfunction "SCL_3") (pintype "passive"))
      (node (ref "P3") (pin "4") (pinfunction "SCLK_4") (pintype "passive"))
      (node (ref "TP12") (pin "1") (pinfunction "1_1") (pintype "passive"))
      (node (ref "U2") (pin "20") (pinfunction "IO12_20") (pintype "passive"))
    )
    (net (code "9") (name "/CS-D1") (class "Default")
      (node (ref "P2") (pin "7") (pinfunction "CS_7") (pintype "passive"))
      (node (ref "TP10") (pin "1") (pinfunction "1_1") (pintype "passive"))
      (node (ref "U2") (pin "18") (pinfunction "IO10_18") (pintype "passive"))
    )
    (net (code "10") (name "/CS-D2") (class "Default")
      (node (ref "P3") (pin "1") (pinfunction "/CS_1") (pintype "passive"))
      (node (ref "TP18") (pin "1") (pinfunction "1_1") (pintype "passive"))
      (node (ref "U2") (pin "11") (pinfunction "IO18_11") (pintype "passive"))
    )
    (net (code "11") (name "/DC-D1") (class "Default")
      (node (ref "P2") (pin "6") (pinfunction "DC_6") (pintype "passive"))
      (node (ref "TP13") (pin "1") (pinfunction "1_1") (pintype "passive"))
      (node (ref "U2") (pin "21") (pinfunction "IO13_21") (pintype "passive"))
    )
    (net (code "12") (name "/DISCHARGE") (class "Default")
      (node (ref "Q1") (pin "1") (pinfunction "G_1") (pintype "passive"))
      (node (ref "Q2") (pin "1") (pinfunction "G_1") (pintype "passive"))
      (node (ref "R11") (pin "1") (pinfunction "1_1") (pintype "passive"))
      (node (ref "TP21") (pin "1") (pinfunction "1_1") (pintype "passive"))
      (node (ref "U2") (pin "23") (pinfunction "IO21_23") (pintype "passive"))
    )
    (net (code "13") (name "/DM") (class "Default")
      (node (ref "P5") (pin "2") (pinfunction "2_2") (pintype "passive"))
      (node (ref "TP19") (pin "1") (pinfunction "1_1") (pintype "passive"))
      (node (ref "U2") (pin "13") (pinfunction "IO19_13") (pintype "passive"))
    )
    (net (code "14") (name "/DP") (class "Default")
      (node (ref "P5") (pin "3") (pinfunction "3_3") (pintype "passive"))
      (node (ref "TP20") (pin "1") (pinfunction "1_1") (pintype "passive"))
      (node (ref "U2") (pin "14") (pinfunction "IO20_14") (pintype "passive"))
    )
    (net (code "15") (name "/EN") (class "Default")
      (node (ref "R1") (pin "1") (pinfunction "1_1") (pintype "passive"))
      (node (ref "S2") (pin "1") (pinfunction "1_1") (pintype "passive"))
      (node (ref "TP22") (pin "1") (pinfunction "1_1") (pintype "passive"))
      (node (ref "U2") (pin "3") (pinfunction "EN_3") (pintype "passive"))
    )
    (net (code "16") (name "/I2C-SCL") (class "Default")
      (node (ref "P4") (pin "4") (pinfunction "4_4") (pintype "passive"))
      (node (ref "R8") (pin "2") (pinfunction "2_2") (pintype "passive"))
      (node (ref "TP3") (pin "1") (pinfunction "1_1") (pintype "passive"))
      (node (ref "U2") (pin "15") (pinfunction "IO3_15") (pintype "passive"))
    )
    (net (code "17") (name "/I2C-SDA") (class "Default")
      (node (ref "P4") (pin "3") (pinfunction "3_3") (pintype "passive"))
      (node (ref "R9") (pin "2") (pinfunction "2_2") (pintype "passive"))
      (node (ref "TP4") (pin "1") (pinfunction "1_1") (pintype "passive"))
      (node (ref "U2") (pin "4") (pinfunction "IO4_4") (pintype "passive"))
    )
    (net (code "18") (name "/LED1") (class "Default")
      (node (ref "R2") (pin "1") (pinfunction "1_1") (pintype "passive"))
      (node (ref "TP6") (pin "1") (pinfunction "1_1") (pintype "passive"))
      (node (ref "U2") (pin "6") (pinfunction "IO6_6") (pintype "passive"))
    )
    (net (code "19") (name "/MISO-D2") (class "Default")
      (node (ref "P3") (pin "6") (pinfunction "SO_6") (pintype "passive"))
      (node (ref "TP9") (pin "1") (pinfunction "1_1") (pintype "passive"))
      (node (ref "U2") (pin "17") (pinfunction "IO9_17") (pintype "passive"))
    )
    (net (code "20") (name "/MODE") (class "Default")
      (node (ref "S3") (pin "1") (pinfunction "1_1") (pintype "passive"))
      (node (ref "TP0") (pin "1") (pinfunction "1_1") (pintype "passive"))
      (node (ref "U2") (pin "27") (pinfunction "IO0_27") (pintype "passive"))
    )
    (net (code "21") (name "/MOSI-SDA") (class "Default")
      (node (ref "P2") (pin "4") (pinfunction "SDA_4") (pintype "passive"))
      (node (ref "P3") (pin "5") (pinfunction "SI_5") (pintype "passive"))
      (node (ref "TP11") (pin "1") (pinfunction "1_1") (pintype "passive"))
      (node (ref "U2") (pin "19") (pinfunction "IO11_19") (pintype "passive"))
    )
    (net (code "22") (name "/NP-DATA") (class "Default")
      (node (ref "D3") (pin "1") (pinfunction "DIN_1") (pintype "passive"))
      (node (ref "TP5") (pin "1") (pinfunction "1_1") (pintype "passive"))
      (node (ref "U2") (pin "5") (pinfunction "IO5_5") (pintype "passive"))
    )
    (net (code "23") (name "/NP-PWR") (class "Default")
      (node (ref "Q3") (pin "G") (pinfunction "G_G") (pintype "passive"))
      (node (ref "R12") (pin "2") (pinfunction "2_2") (pintype "passive"))
      (node (ref "TP48") (pin "1") (pinfunction "1_1") (pintype "passive"))
      (node (ref "U2") (pin "25") (pinfunction "IO48_25") (pintype "passive"))
    )
    (net (code "24") (name "/RESET-D1") (class "Default")
      (node (ref "P2") (pin "5") (pinfunction "RES_5") (pintype "passive"))
      (node (ref "TP8") (pin "1") (pinfunction "1_1") (pintype "passive"))
      (node (ref "U2") (pin "12") (pinfunction "IO8_12") (pintype "passive"))
    )
    (net (code "25") (name "/RESET-D2") (class "Default")
      (node (ref "P3") (pin "7") (pinfunction "/RESET_7") (pintype "passive"))
      (node (ref "TP45") (pin "1") (pinfunction "1_1") (pintype "passive"))
      (node (ref "U2") (pin "26") (pinfunction "IO45_26") (pintype "passive"))
    )
    (net (code "26") (name "/RXD-IN") (class "Default")
      (node (ref "P1") (pin "4") (pinfunction "4_4") (pintype "passive"))
      (node (ref "TP24") (pin "1") (pinfunction "1_1") (pintype "passive"))
      (node (ref "U2") (pin "36") (pinfunction "RXD0_36") (pintype "passive"))
    )
    (net (code "27") (name "/TXD-OUT") (class "Default")
      (node (ref "P1") (pin "3") (pinfunction "3_3") (pintype "passive"))
      (node (ref "TP23") (pin "1") (pinfunction "1_1") (pintype "passive"))
      (node (ref "U2") (pin "37") (pinfunction "TXD0_37") (pintype "passive"))
    )
    (net (code "28") (name "/VSTVC") (class "Default")
      (node (ref "C14") (pin "2") (pinfunction "2_2") (pintype "passive"))
      (node (ref "P3") (pin "39") (pinfunction "VST_39") (pintype "passive"))
      (node (ref "P3") (pin "40") (pinfunction "VCOM_PANEL_40") (pintype "passive"))
      (node (ref "R10") (pin "1") (pinfunction "1_1") (pintype "passive"))
    )
    (net (code "29") (name "3.3V") (class "Default")
      (node (ref "C1") (pin "1") (pinfunction "1_1") (pintype "passive"))
      (node (ref "C3") (pin "1") (pinfunction "1_1") (pintype "passive"))
      (node (ref "C4") (pin "1") (pinfunction "1_1") (pintype "passive"))
      (node (ref "P2") (pin "2") (pinfunction "VCC_2") (pintype "passive"))
      (node (ref "P3") (pin "31") (pinfunction "VCC_31") (pintype "passive"))
      (node (ref "P3") (pin "32") (pinfunction "VDD_32") (pintype "passive"))
      (node (ref "P4") (pin "2") (pinfunction "2_2") (pintype "passive"))
      (node (ref "Q3") (pin "S") (pinfunction "S_S") (pintype "passive"))
      (node (ref "R1") (pin "2") (pinfunction "2_2") (pintype "passive"))
      (node (ref "R12") (pin "1") (pinfunction "1_1") (pintype "passive"))
      (node (ref "R3") (pin "2") (pinfunction "2_2") (pintype "passive"))
      (node (ref "R4") (pin "2") (pinfunction "2_2") (pintype "passive"))
      (node (ref "R5") (pin "2") (pinfunction "2_2") (pintype "passive"))
      (node (ref "R6") (pin "2") (pinfunction "2_2") (pintype "passive"))
      (node (ref "R7") (pin "2") (pinfunction "2_2") (pintype "passive"))
      (node (ref "R8") (pin "1") (pinfunction "1_1") (pintype "passive"))
      (node (ref "R9") (pin "1") (pinfunction "1_1") (pintype "passive"))
      (node (ref "U1") (pin "3") (pinfunction "VOUT_3") (pintype "passive"))
      (node (ref "U2") (pin "2") (pinfunction "3V3_2") (pintype "passive"))
    )
    (net (code "30") (name "5V") (class "Default")
      (node (ref "P1") (pin "1") (pinfunction "1_1") (pintype "passive"))
      (node (ref "P5") (pin "1") (pinfunction "1_1") (pintype "passive"))
      (node (ref "S1") (pin "1") (pinfunction "1_1") (pintype "passive"))
    )
    (net (code "31") (name "GND") (class "Default")
      (node (ref "C1") (pin "2") (pinfunction "2_2") (pintype "passive"))
      (node (ref "C14") (pin "1") (pinfunction "1_1") (pintype "passive"))
      (node (ref "C16") (pin "2") (pinfunction "2_2") (pintype "passive"))
      (node (ref "C17") (pin "2") (pinfunction "2_2") (pintype "passive"))
      (node (ref "C18") (pin "2") (pinfunction "2_2") (pintype "passive"))
      (node (ref "C19") (pin "2") (pinfunction "2_2") (pintype "passive"))
      (node (ref "C2") (pin "2") (pinfunction "2_2") (pintype "passive"))
      (node (ref "C20") (pin "2") (pinfunction "2_2") (pintype "passive"))
      (node (ref "C21") (pin "2") (pinfunction "2_2") (pintype "passive"))
      (node (ref "C3") (pin "2") (pinfunction "2_2") (pintype "passive"))
      (node (ref "C4") (pin "2") (pinfunction "2_2") (pintype "passive"))
      (node (ref "C5") (pin "1") (pinfunction "1_1") (pintype "passive"))
      (node (ref "D1") (pin "2") (pinfunction "K_2") (pintype "passive"))
      (node (ref "D2") (pin "1") (pinfunction "K_1") (pintype "passive"))
      (node (ref "D3") (pin "3") (pinfunction "GND_3") (pintype "passive"))
      (node (ref "D4") (pin "3") (pinfunction "GND_3") (pintype "passive"))
      (node (ref "D5") (pin "3") (pinfunction "GND_3") (pintype "passive"))
      (node (ref "D6") (pin "3") (pinfunction "GND_3") (pintype "passive"))
      (node (ref "P1") (pin "2") (pinfunction "2_2") (pintype "passive"))
      (node (ref "P2") (pin "1") (pinfunction "GND_1") (pintype "passive"))
      (node (ref "P3") (pin "3") (pinfunction "ID_3") (pintype "passive"))
      (node (ref "P3") (pin "33") (pinfunction "VSS_33") (pintype "passive"))
      (node (ref "P4") (pin "1") (pinfunction "1_1") (pintype "passive"))
      (node (ref "P5") (pin "4") (pinfunction "4_4") (pintype "passive"))
      (node (ref "Q1") (pin "2") (pinfunction "S_2") (pintype "passive"))
      (node (ref "Q2") (pin "2") (pinfunction "S_2") (pintype "passive"))
      (node (ref "R11") (pin "2") (pinfunction "2_2") (pintype "passive"))
      (node (ref "S2") (pin "2") (pinfunction "2_2") (pintype "passive"))
      (node (ref "S3") (pin "2") (pinfunction "2_2") (pintype "passive"))
      (node (ref "S4") (pin "2") (pinfunction "2_2") (pintype "passive"))
      (node (ref "S5") (pin "2") (pinfunction "2_2") (pintype "passive"))
      (node (ref "S6") (pin "2") (pinfunction "2_2") (pintype "passive"))
      (node (ref "S7") (pin "2") (pinfunction "2_2") (pintype "passive"))
      (node (ref "U1") (pin "2") (pinfunction "GND_2") (pintype "passive"))
      (node (ref "U1") (pin "4") (pinfunction "TAB_4") (pintype "passive"))
      (node (ref "U2") (pin "1") (pinfunction "GND_1") (pintype "passive"))
      (node (ref "U2") (pin "40") (pinfunction "GND_40") (pintype "passive"))
    )
    (net (code "32") (name "Net-(D1-A)") (class "Default")
      (node (ref "D1") (pin "1") (pinfunction "A_1") (pintype "passive"))
      (node (ref "R2") (pin "2") (pinfunction "2_2") (pintype "passive"))
    )
    (net (code "33") (name "Net-(D2-A)") (class "Default")
      (node (ref "C17") (pin "1") (pinfunction "1_1") (pintype "passive"))
      (node (ref "D2") (pin "2") (pinfunction "A_2") (pintype "passive"))
      (node (ref "P3") (pin "35") (pinfunction "VGL_35") (pintype "passive"))
    )
    (net (code "34") (name "Net-(D3-DOUT)") (class "Default")
      (node (ref "D3") (pin "4") (pinfunction "DOUT_4") (pintype "passive"))
      (node (ref "D4") (pin "1") (pinfunction "DIN_1") (pintype "passive"))
    )
    (net (code "35") (name "Net-(D3-VDD)") (class "Default")
      (node (ref "C19") (pin "1") (pinfunction "1_1") (pintype "passive"))
      (node (ref "C20") (pin "1") (pinfunction "1_1") (pintype "passive"))
      (node (ref "D3") (pin "2") (pinfunction "VDD_2") (pintype "passive"))
      (node (ref "D4") (pin "2") (pinfunction "VDD_2") (pintype "passive"))
      (node (ref "D5") (pin "2") (pinfunction "VDD_2") (pintype "passive"))
      (node (ref "D6") (pin "2") (pinfunction "VDD_2") (pintype "passive"))
      (node (ref "Q3") (pin "D") (pinfunction "D_D") (pintype "passive"))
    )
    (net (code "36") (name "Net-(D4-DOUT)") (class "Default")
      (node (ref "D4") (pin "4") (pinfunction "DOUT_4") (pintype "passive"))
      (node (ref "D5") (pin "1") (pinfunction "DIN_1") (pintype "passive"))
    )
    (net (code "37") (name "Net-(D5-DOUT)") (class "Default")
      (node (ref "D5") (pin "4") (pinfunction "DOUT_4") (pintype "passive"))
      (node (ref "D6") (pin "1") (pinfunction "DIN_1") (pintype "passive"))
    )
    (net (code "38") (name "Net-(P3-C11M)") (class "Default")
      (node (ref "C15") (pin "2") (pinfunction "2_2") (pintype "passive"))
      (node (ref "P3") (pin "28") (pinfunction "C11M_28") (pintype "passive"))
    )
    (net (code "39") (name "Net-(P3-C11P)") (class "Default")
      (node (ref "C15") (pin "1") (pinfunction "1_1") (pintype "passive"))
      (node (ref "P3") (pin "29") (pinfunction "C11P_29") (pintype "passive"))
    )
    (net (code "40") (name "Net-(P3-C12M)") (class "Default")
      (node (ref "C13") (pin "2") (pinfunction "2_2") (pintype "passive"))
      (node (ref "P3") (pin "26") (pinfunction "C12M_26") (pintype "passive"))
    )
    (net (code "41") (name "Net-(P3-C12P)") (class "Default")
      (node (ref "C13") (pin "1") (pinfunction "1_1") (pintype "passive"))
      (node (ref "P3") (pin "27") (pinfunction "C12P_27") (pintype "passive"))
    )
    (net (code "42") (name "Net-(P3-C13M)") (class "Default")
      (node (ref "C12") (pin "2") (pinfunction "2_2") (pintype "passive"))
      (node (ref "P3") (pin "24") (pinfunction "C13M_24") (pintype "passive"))
    )
    (net (code "43") (name "Net-(P3-C13P)") (class "Default")
      (node (ref "C12") (pin "1") (pinfunction "1_1") (pintype "passive"))
      (node (ref "P3") (pin "25") (pinfunction "C13P_25") (pintype "passive"))
    )
    (net (code "44") (name "Net-(P3-C14M)") (class "Default")
      (node (ref "C11") (pin "2") (pinfunction "2_2") (pintype "passive"))
      (node (ref "P3") (pin "22") (pinfunction "C14M_22") (pintype "passive"))
    )
    (net (code "45") (name "Net-(P3-C14P)") (class "Default")
      (node (ref "C11") (pin "1") (pinfunction "1_1") (pintype "passive"))
      (node (ref "P3") (pin "23") (pinfunction "C14P_23") (pintype "passive"))
    )
    (net (code "46") (name "Net-(P3-C15M)") (class "Default")
      (node (ref "C10") (pin "2") (pinfunction "2_2") (pintype "passive"))
      (node (ref "P3") (pin "20") (pinfunction "C15M_20") (pintype "passive"))
    )
    (net (code "47") (name "Net-(P3-C15P)") (class "Default")
      (node (ref "C10") (pin "1") (pinfunction "1_1") (pintype "passive"))
      (node (ref "P3") (pin "21") (pinfunction "C15P_21") (pintype "passive"))
    )
    (net (code "48") (name "Net-(P3-C16M)") (class "Default")
      (node (ref "C9") (pin "1") (pinfunction "1_1") (pintype "passive"))
      (node (ref "P3") (pin "18") (pinfunction "C16M_18") (pintype "passive"))
    )
    (net (code "49") (name "Net-(P3-C16P)") (class "Default")
      (node (ref "C9") (pin "2") (pinfunction "2_2") (pintype "passive"))
      (node (ref "P3") (pin "19") (pinfunction "C16P_19") (pintype "passive"))
    )
    (net (code "50") (name "Net-(P3-C21M)") (class "Default")
      (node (ref "C8") (pin "1") (pinfunction "1_1") (pintype "passive"))
      (node (ref "P3") (pin "16") (pinfunction "C21M_16") (pintype "passive"))
    )
    (net (code "51") (name "Net-(P3-C21P)") (class "Default")
      (node (ref "C8") (pin "2") (pinfunction "2_2") (pintype "passive"))
      (node (ref "P3") (pin "17") (pinfunction "C21P_17") (pintype "passive"))
    )
    (net (code "52") (name "Net-(P3-C31M)") (class "Default")
      (node (ref "C7") (pin "1") (pinfunction "1_1") (pintype "passive"))
      (node (ref "P3") (pin "14") (pinfunction "C31M_14") (pintype "passive"))
    )
    (net (code "53") (name "Net-(P3-C31P)") (class "Default")
      (node (ref "C7") (pin "2") (pinfunction "2_2") (pintype "passive"))
      (node (ref "P3") (pin "15") (pinfunction "C31P_15") (pintype "passive"))
    )
    (net (code "54") (name "Net-(P3-C41M)") (class "Default")
      (node (ref "C6") (pin "2") (pinfunction "2_2") (pintype "passive"))
      (node (ref "P3") (pin "13") (pinfunction "C41M_13") (pintype "passive"))
    )
    (net (code "55") (name "Net-(P3-C41P)") (class "Default")
      (node (ref "C6") (pin "1") (pinfunction "1_1") (pintype "passive"))
      (node (ref "P3") (pin "12") (pinfunction "C41P_12") (pintype "passive"))
    )
    (net (code "56") (name "Net-(P3-VCL)") (class "Default")
      (node (ref "C5") (pin "2") (pinfunction "2_2") (pintype "passive"))
      (node (ref "P3") (pin "9") (pinfunction "VCL_9") (pintype "passive"))
    )
    (net (code "57") (name "Net-(P3-VCOM_DRIVER)") (class "Default")
      (node (ref "P3") (pin "30") (pinfunction "VCOM_DRIVER_30") (pintype "passive"))
      (node (ref "R10") (pin "2") (pinfunction "2_2") (pintype "passive"))
    )
    (net (code "58") (name "Net-(P3-VDH)") (class "Default")
      (node (ref "C18") (pin "1") (pinfunction "1_1") (pintype "passive"))
      (node (ref "P3") (pin "36") (pinfunction "VDH_36") (pintype "passive"))
      (node (ref "Q2") (pin "3") (pinfunction "D_3") (pintype "passive"))
    )
    (net (code "59") (name "Net-(P3-VDL)") (class "Default")
      (node (ref "C21") (pin "1") (pinfunction "1_1") (pintype "passive"))
      (node (ref "P3") (pin "37") (pinfunction "VDL_37") (pintype "passive"))
    )
    (net (code "60") (name "Net-(P3-VGH)") (class "Default")
      (node (ref "C16") (pin "1") (pinfunction "1_1") (pintype "passive"))
      (node (ref "P3") (pin "34") (pinfunction "VGH_34") (pintype "passive"))
      (node (ref "Q1") (pin "3") (pinfunction "D_3") (pintype "passive"))
    )
    (net (code "61") (name "Net-(U2-IO1)") (class "Default")
      (node (ref "TP1") (pin "1") (pinfunction "1_1") (pintype "passive"))
      (node (ref "U2") (pin "39") (pinfunction "IO1_39") (pintype "passive"))
    )
    (net (code "62") (name "Net-(U2-IO2)") (class "Default")
      (node (ref "TP2") (pin "1") (pinfunction "1_1") (pintype "passive"))
      (node (ref "U2") (pin "38") (pinfunction "IO2_38") (pintype "passive"))
    )
    (net (code "63") (name "Net-(U2-IO14)") (class "Default")
      (node (ref "TP14") (pin "1") (pinfunction "1_1") (pintype "passive"))
      (node (ref "U2") (pin "22") (pinfunction "IO14_22") (pintype "passive"))
    )
    (net (code "64") (name "Net-(U2-IO35)") (class "Default")
      (node (ref "TP35") (pin "1") (pinfunction "1_1") (pintype "passive"))
      (node (ref "U2") (pin "28") (pinfunction "IO35_28") (pintype "passive"))
    )
    (net (code "65") (name "Net-(U2-IO36)") (class "Default")
      (node (ref "TP36") (pin "1") (pinfunction "1_1") (pintype "passive"))
      (node (ref "U2") (pin "29") (pinfunction "IO36_29") (pintype "passive"))
    )
    (net (code "66") (name "Net-(U2-IO37)") (class "Default")
      (node (ref "TP37") (pin "1") (pinfunction "1_1") (pintype "passive"))
      (node (ref "U2") (pin "30") (pinfunction "IO37_30") (pintype "passive"))
    )
    (net (code "67") (name "Net-(U2-IO39)") (class "Default")
      (node (ref "TP39") (pin "1") (pinfunction "1_1") (pintype "passive"))
      (node (ref "U2") (pin "32") (pinfunction "IO39_32") (pintype "passive"))
    )
    (net (code "68") (name "Net-(U2-IO40)") (class "Default")
      (node (ref "TP40") (pin "1") (pinfunction "1_1") (pintype "passive"))
      (node (ref "U2") (pin "33") (pinfunction "IO40_33") (pintype "passive"))
    )
    (net (code "69") (name "Net-(U2-IO41)") (class "Default")
      (node (ref "TP41") (pin "1") (pinfunction "1_1") (pintype "passive"))
      (node (ref "U2") (pin "34") (pinfunction "IO41_34") (pintype "passive"))
    )
    (net (code "70") (name "Net-(U2-IO42)") (class "Default")
      (node (ref "TP42") (pin "1") (pinfunction "1_1") (pintype "passive"))
      (node (ref "U2") (pin "35") (pinfunction "IO42_35") (pintype "passive"))
    )
    (net (code "71") (name "Net-(U2-IO46)") (class "Default")
      (node (ref "TP46") (pin "1") (pinfunction "1_1") (pintype "passive"))
      (node (ref "U2") (pin "16") (pinfunction "IO46_16") (pintype "passive"))
    )
    (net (code "72") (name "VBAT") (class "Default")
      (node (ref "P5") (pin "5") (pinfunction "5_5") (pintype "passive"))
      (node (ref "S1") (pin "3") (pinfunction "3_3") (pintype "passive"))
    )
    (net (code "73") (name "VCC") (class "Default")
      (node (ref "C2") (pin "1") (pinfunction "1_1") (pintype "passive"))
      (node (ref "S1") (pin "2") (pinfunction "2_2") (pintype "passive"))
      (node (ref "U1") (pin "1") (pinfunction "VIN_1") (pintype "passive"))
    )
    (net (code "74") (name "unconnected-(D6-DOUT-Pad4)") (class "Default")
      (node (ref "D6") (pin "4") (pinfunction "DOUT_4") (pintype "passive+no_connect"))
    )
    (net (code "75") (name "unconnected-(P3-C42M-Pad11)") (class "Default")
      (node (ref "P3") (pin "11") (pinfunction "C42M_11") (pintype "passive+no_connect"))
    )
    (net (code "76") (name "unconnected-(P3-C42P-Pad10)") (class "Default")
      (node (ref "P3") (pin "10") (pinfunction "C42P_10") (pintype "passive+no_connect"))
    )
  )
)
